# 1_Controller_A20_Power.net
KiCad netlist of a schematic drawn in Altium Designer
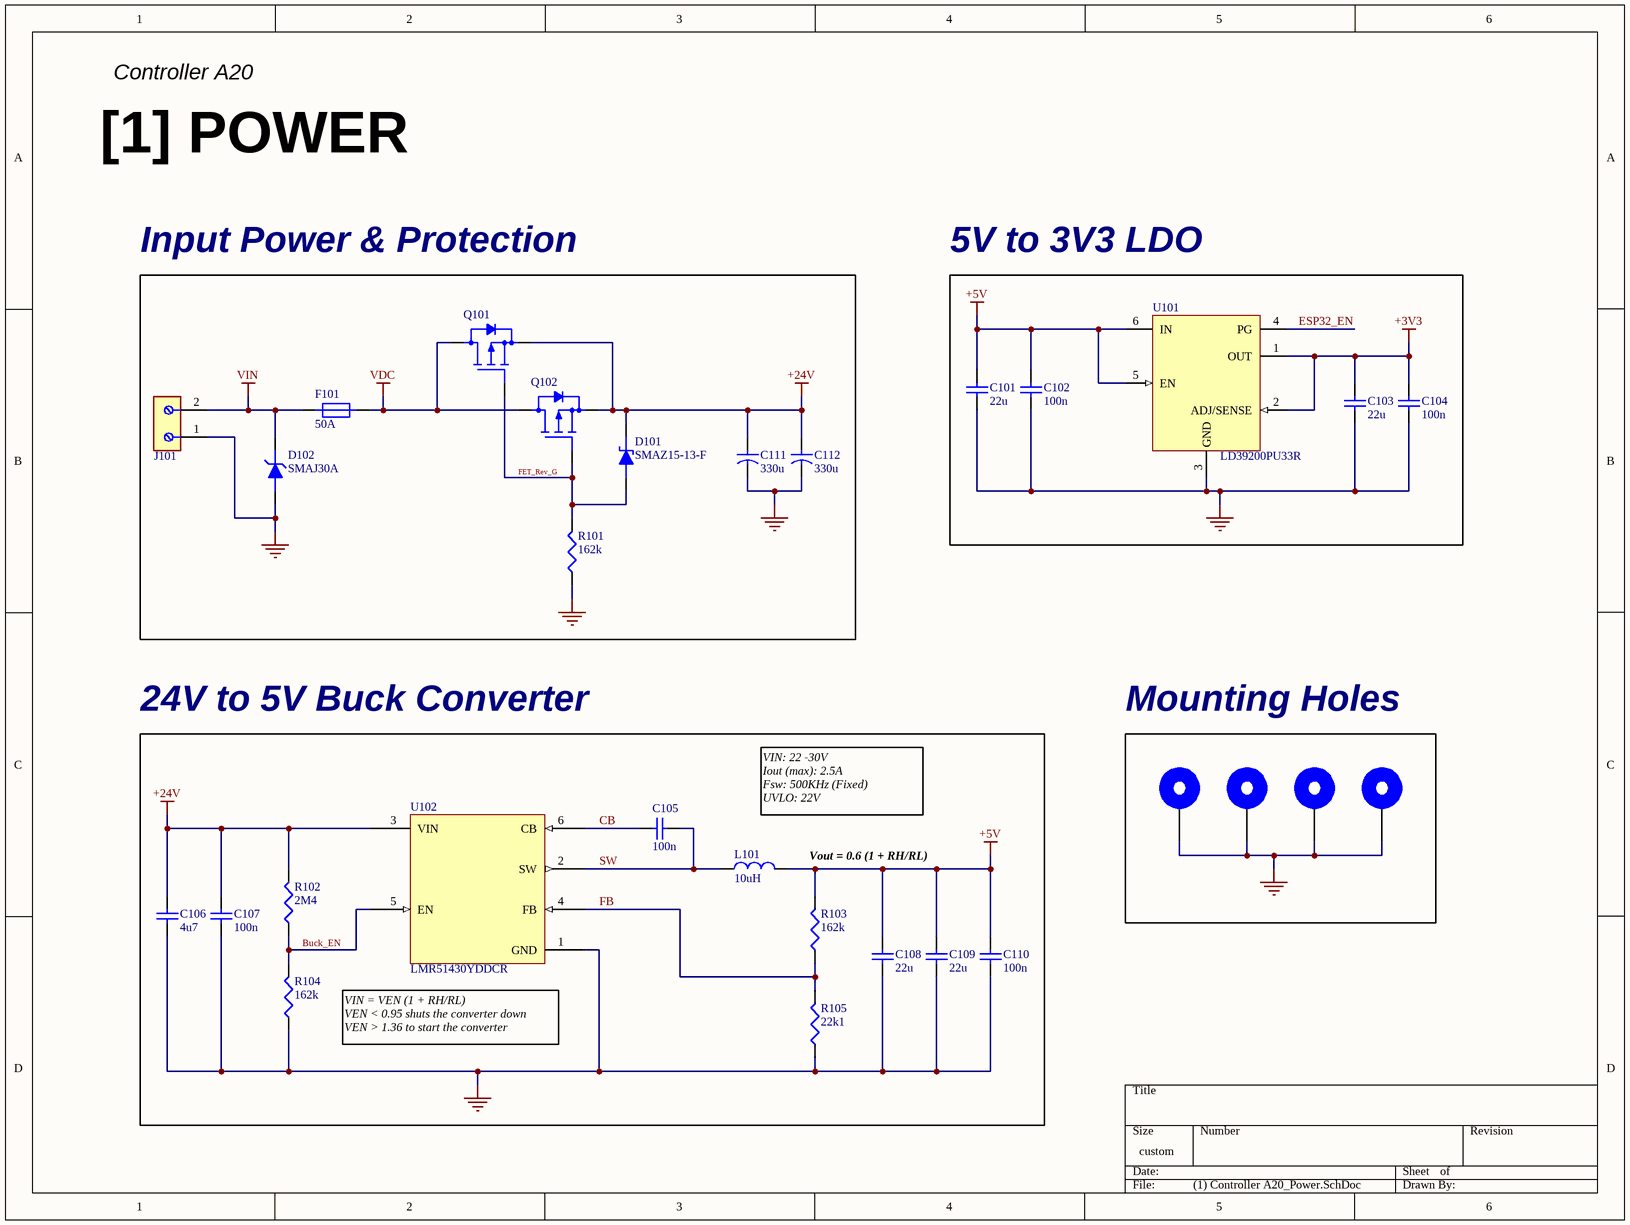
[diagram p0: (1) Controller A20_Power.SchDoc]

(export (version "E")
  (design (tool "Eeschema 10.0.6"))
  (components
    (comp (ref "C101")
      (value "22u")
      (footprint "C0805")
      (description "22 µF ±20% 25V Ceramic Capacitor X5R 0805 (2012 Metric)")
      (fields
        (field (name "MANUFACTURER") "Samsung Electro-Mechanics")
        (field (name "MFR. PART #") "CL21A226MAYNNNE")
      )
      (libsource (lib "Symbols") (part "CAP 22uF 25V"))
    )
    (comp (ref "C102")
      (value "100n")
      (footprint "C0603")
      (description "0.1 µF ±10% 50V Ceramic Capacitor X7R 0603 (1608 Metric)")
      (fields (field (name "MANUFACTURER") "KEMET") (field (name "MFR. PART #") "C0603C104K5RACTU"))
      (libsource (lib "Symbols") (part "CAP 100nF 50V"))
    )
    (comp (ref "C103")
      (value "22u")
      (footprint "C0805")
      (description "22 µF ±20% 25V Ceramic Capacitor X5R 0805 (2012 Metric)")
      (fields
        (field (name "MANUFACTURER") "Samsung Electro-Mechanics")
        (field (name "MFR. PART #") "CL21A226MAYNNNE")
      )
      (libsource (lib "Symbols") (part "CAP 22uF 25V"))
    )
    (comp (ref "C104")
      (value "100n")
      (footprint "C0603")
      (description "0.1 µF ±10% 50V Ceramic Capacitor X7R 0603 (1608 Metric)")
      (fields (field (name "MANUFACTURER") "KEMET") (field (name "MFR. PART #") "C0603C104K5RACTU"))
      (libsource (lib "Symbols") (part "CAP 100nF 50V"))
    )
    (comp (ref "C105")
      (value "100n")
      (footprint "C0603")
      (description "0.1 µF ±10% 50V Ceramic Capacitor X7R 0603 (1608 Metric)")
      (fields (field (name "MANUFACTURER") "KEMET") (field (name "MFR. PART #") "C0603C104K5RACTU"))
      (libsource (lib "Symbols") (part "CAP 100nF 50V"))
    )
    (comp (ref "C106")
      (value "4u7")
      (footprint "C0805")
      (description "4.7 µF ±20% 50V Ceramic Capacitor X7R 0805 (2012 Metric)")
      (fields
        (field (name "MANUFACTURER") "Murata Electronics")
        (field (name "MFR. PART #") "GRM21BZ71H475ME15K")
      )
      (libsource (lib "Symbols") (part "CAP 4.7uF 50V"))
    )
    (comp (ref "C107")
      (value "100n")
      (footprint "C0603")
      (description "0.1 µF ±10% 50V Ceramic Capacitor X7R 0603 (1608 Metric)")
      (fields (field (name "MANUFACTURER") "KEMET") (field (name "MFR. PART #") "C0603C104K5RACTU"))
      (libsource (lib "Symbols") (part "CAP 100nF 50V"))
    )
    (comp (ref "C108")
      (value "22u")
      (footprint "C0805")
      (description "22 µF ±20% 25V Ceramic Capacitor X5R 0805 (2012 Metric)")
      (fields
        (field (name "MANUFACTURER") "Samsung Electro-Mechanics")
        (field (name "MFR. PART #") "CL21A226MAYNNNE")
      )
      (libsource (lib "Symbols") (part "CAP 22uF 25V"))
    )
    (comp (ref "C109")
      (value "22u")
      (footprint "C0805")
      (description "22 µF ±20% 25V Ceramic Capacitor X5R 0805 (2012 Metric)")
      (fields
        (field (name "MANUFACTURER") "Samsung Electro-Mechanics")
        (field (name "MFR. PART #") "CL21A226MAYNNNE")
      )
      (libsource (lib "Symbols") (part "CAP 22uF 25V"))
    )
    (comp (ref "C110")
      (value "100n")
      (footprint "C0603")
      (description "0.1 µF ±10% 50V Ceramic Capacitor X7R 0603 (1608 Metric)")
      (fields (field (name "MANUFACTURER") "KEMET") (field (name "MFR. PART #") "C0603C104K5RACTU"))
      (libsource (lib "Symbols") (part "CAP 100nF 50V"))
    )
    (comp (ref "C111")
      (value "330u")
      (footprint "SMD CAP,D10.3xL10.3mm")
      (description "330 µF 50 V Aluminum Electrolytic Capacitors Radial, Can - SMD 2000 Hrs @ 105°C")
      (fields (field (name "MANUFACTURER") "Nichicon") (field (name "MFR. PART #") "UCM1H331MNL1GS"))
      (libsource (lib "Symbols") (part "Electrolytic CAP 330uF 50V"))
    )
    (comp (ref "C112")
      (value "330u")
      (footprint "SMD CAP,D10.3xL10.3mm")
      (description "330 µF 50 V Aluminum Electrolytic Capacitors Radial, Can - SMD 2000 Hrs @ 105°C")
      (fields (field (name "MANUFACTURER") "Nichicon") (field (name "MFR. PART #") "UCM1H331MNL1GS"))
      (libsource (lib "Symbols") (part "Electrolytic CAP 330uF 50V"))
    )
    (comp (ref "D101")
      (value "SMAZ15-13-F")
      (footprint "DO-214AC(SMA)")
      (description "Zener Diode 15 V 1 W ±5% Surface Mount SMA")
      (fields (field (name "MANUFACTURER") "Diodes Incorporated"))
      (libsource (lib "Symbols") (part "SMAZ15-13-F 15V Zener Diode"))
    )
    (comp (ref "D102")
      (value "SMAJ30A")
      (footprint "DO-214AC(SMA)")
      (description "48.4V Clamp 8.3A Ipp Tvs Diode Surface Mount DO-214AC")
      (fields (field (name "MANUFACTURER") "Würth Elektronik"))
      (libsource (lib "Symbols") (part "SMAJ30A TVS Diode 30VRWM"))
    )
    (comp (ref "F101")
      (value "50A")
      (footprint "SMD Fuse,12.2 x 4.5 x 4.5 mm")
      (description "50 A 250 V 80 V Fuse Board Mount (Cartridge Style Excluded) Surface Mount 2-SMD, Square End Block")
      (fields (field (name "MANUFACTURER") "Littelfuse Inc.") (field (name "MFR. PART #") "0456050.DRSDE"))
      (libsource (lib "Symbols") (part "0456050.DRSDE Fuse 50A"))
    )
    (comp (ref "J101")
      (value "691256610002")
      (footprint "10.16mm 2P STB")
      (description "2 Position Wire to Board Terminal Block Horizontal with Board 0.400\" (10.16mm) Through Hole")
      (fields (field (name "MANUFACTURER") "Würth Elektronik"))
      (libsource (lib "Symbols") (part "Terminal Block 2P 57A"))
    )
    (comp (ref "J102")
      (value "Mounting Hole D6mm H3mm")
      (footprint "MH D6mm H3mm")
      (libsource (lib "Symbols") (part "Mounting Hole D6mm H3mm"))
    )
    (comp (ref "J103")
      (value "Mounting Hole D6mm H3mm")
      (footprint "MH D6mm H3mm")
      (libsource (lib "Symbols") (part "Mounting Hole D6mm H3mm"))
    )
    (comp (ref "J104")
      (value "Mounting Hole D6mm H3mm")
      (footprint "MH D6mm H3mm")
      (libsource (lib "Symbols") (part "Mounting Hole D6mm H3mm"))
    )
    (comp (ref "J105")
      (value "Mounting Hole D6mm H3mm")
      (footprint "MH D6mm H3mm")
      (libsource (lib "Symbols") (part "Mounting Hole D6mm H3mm"))
    )
    (comp (ref "L101")
      (value "10uH")
      (footprint "L SMD 6.8x6.6")
      (description "10 µH Shielded Inductor 7 A 29.82mOhm Max Nonstandard")
      (fields (field (name "MANUFACTURER") "Pulse Electronics") (field (name "MFR. PART #") "PM5432.103NLT"))
      (libsource (lib "Symbols") (part "10uH 7A Inductor"))
    )
    (comp (ref "Q101")
      (value "XPH3R114MC,L1XHQ")
      (footprint "8-SOP Advance (5x5)")
      (description "P-Channel 40 V 100A (Ta) 960mW (Ta), 170W (Tc) Surface Mount 8-SOP Advance (5x5)")
      (fields (field (name "MANUFACTURER") "Toshiba Semiconductor and Storage"))
      (libsource (lib "Symbols") (part "MOSFET P-CH 40V 100A"))
    )
    (comp (ref "Q102")
      (value "XPH3R114MC,L1XHQ")
      (footprint "8-SOP Advance (5x5)")
      (description "P-Channel 40 V 100A (Ta) 960mW (Ta), 170W (Tc) Surface Mount 8-SOP Advance (5x5)")
      (fields (field (name "MANUFACTURER") "Toshiba Semiconductor and Storage"))
      (libsource (lib "Symbols") (part "MOSFET P-CH 40V 100A"))
    )
    (comp (ref "R101")
      (value "162k")
      (footprint "R0603")
      (description "162 kOhms ±1% 0.1W, 1/10W Chip Resistor 0603 (1608 Metric) Moisture Resistant Thick Film")
      (fields (field (name "MANUFACTURER") "YAGEO") (field (name "MFR. PART #") "RC0603FR-07162KL"))
      (libsource (lib "Symbols") (part "RES 162k"))
    )
    (comp (ref "R102")
      (value "2M4")
      (footprint "R0603")
      (description "2.4 MOhms ±1% 0.1W, 1/10W Chip Resistor 0603 (1608 Metric) Moisture Resistant Thick Film")
      (fields (field (name "MANUFACTURER") "YAGEO") (field (name "MFR. PART #") "RC0603FR-072M4L"))
      (libsource (lib "Symbols") (part "RES 2.4M"))
    )
    (comp (ref "R103")
      (value "162k")
      (footprint "R0603")
      (description "162 kOhms ±1% 0.1W, 1/10W Chip Resistor 0603 (1608 Metric) Moisture Resistant Thick Film")
      (fields (field (name "MANUFACTURER") "YAGEO") (field (name "MFR. PART #") "RC0603FR-07162KL"))
      (libsource (lib "Symbols") (part "RES 162k"))
    )
    (comp (ref "R104")
      (value "162k")
      (footprint "R0603")
      (description "162 kOhms ±1% 0.1W, 1/10W Chip Resistor 0603 (1608 Metric) Moisture Resistant Thick Film")
      (fields (field (name "MANUFACTURER") "YAGEO") (field (name "MFR. PART #") "RC0603FR-07162KL"))
      (libsource (lib "Symbols") (part "RES 162k"))
    )
    (comp (ref "R105")
      (value "22k1")
      (footprint "R0603")
      (description "22.1 kOhms ±1% 0.1W, 1/10W Chip Resistor 0603 (1608 Metric) Thin Film")
      (fields (field (name "MANUFACTURER") "YAGEO") (field (name "MFR. PART #") "RT0603FRE0722K1L"))
      (libsource (lib "Symbols") (part "RES 22.1k"))
    )
    (comp (ref "U101")
      (value "LD39200PU33R")
      (footprint "DFN-6(3x3)")
      (description "Linear Voltage Regulator IC Positive Fixed 1 Output 2A 6-DFN (3x3)")
      (fields (field (name "MANUFACTURER") "STMicroelectronics"))
      (libsource (lib "Symbols") (part "LDO 3V3 2A"))
    )
    (comp (ref "U102")
      (value "LMR51430YDDCR")
      (footprint "SOT-23-6")
      (description "Buck Switching Regulator IC Positive Adjustable 0.6V 1 Output 3A SOT-23-6 Thin, TSOT-23-6")
      (fields (field (name "MANUFACTURER") "Texas Instruments"))
      (libsource (lib "Symbols") (part "LMR51430YDDCR Buck Converter"))
    )
  )
  (nets
    (net (code "1") (name "+3V3") (class "Default")
      (node (ref "C103") (pin "2") (pinfunction "2_2") (pintype "passive"))
      (node (ref "C104") (pin "2") (pinfunction "2_2") (pintype "passive"))
      (node (ref "U101") (pin "1") (pinfunction "OUT_1") (pintype "power_in"))
      (node (ref "U101") (pin "2") (pinfunction "ADJ/SENSE_2") (pintype "input"))
    )
    (net (code "2") (name "+5V") (class "Default")
      (node (ref "C101") (pin "2") (pinfunction "2_2") (pintype "passive"))
      (node (ref "C102") (pin "2") (pinfunction "2_2") (pintype "passive"))
      (node (ref "C108") (pin "2") (pinfunction "2_2") (pintype "passive"))
      (node (ref "C109") (pin "2") (pinfunction "2_2") (pintype "passive"))
      (node (ref "C110") (pin "2") (pinfunction "2_2") (pintype "passive"))
      (node (ref "L101") (pin "2") (pinfunction "2_2") (pintype "passive"))
      (node (ref "R103") (pin "2") (pinfunction "2_2") (pintype "passive"))
      (node (ref "U101") (pin "5") (pinfunction "EN_5") (pintype "input"))
      (node (ref "U101") (pin "6") (pinfunction "IN_6") (pintype "power_in"))
    )
    (net (code "3") (name "+24V") (class "Default")
      (node (ref "C106") (pin "2") (pinfunction "2_2") (pintype "passive"))
      (node (ref "C107") (pin "2") (pinfunction "2_2") (pintype "passive"))
      (node (ref "C111") (pin "1") (pinfunction "1_1") (pintype "passive"))
      (node (ref "C112") (pin "1") (pinfunction "1_1") (pintype "passive"))
      (node (ref "D101") (pin "2") (pinfunction "2_2") (pintype "passive"))
      (node (ref "Q101") (pin "1") (pinfunction "1_1") (pintype "passive"))
      (node (ref "Q102") (pin "1") (pinfunction "1_1") (pintype "passive"))
      (node (ref "R102") (pin "2") (pinfunction "2_2") (pintype "passive"))
      (node (ref "U102") (pin "3") (pinfunction "VIN_3") (pintype "power_in"))
    )
    (net (code "4") (name "/Buck_EN") (class "Default")
      (node (ref "R102") (pin "1") (pinfunction "1_1") (pintype "passive"))
      (node (ref "R104") (pin "2") (pinfunction "2_2") (pintype "passive"))
      (node (ref "U102") (pin "5") (pinfunction "EN_5") (pintype "input"))
    )
    (net (code "5") (name "/CB") (class "Default")
      (node (ref "C105") (pin "1") (pinfunction "1_1") (pintype "passive"))
      (node (ref "U102") (pin "6") (pinfunction "CB_6") (pintype "input"))
    )
    (net (code "6") (name "/ESP32_EN") (class "Default")
      (node (ref "U101") (pin "4") (pinfunction "PG_4") (pintype "tri_state"))
    )
    (net (code "7") (name "/FB") (class "Default")
      (node (ref "R103") (pin "1") (pinfunction "1_1") (pintype "passive"))
      (node (ref "R105") (pin "2") (pinfunction "2_2") (pintype "passive"))
      (node (ref "U102") (pin "4") (pinfunction "FB_4") (pintype "input"))
    )
    (net (code "8") (name "/FET_Rev_G") (class "Default")
      (node (ref "D101") (pin "1") (pinfunction "1_1") (pintype "passive"))
      (node (ref "Q101") (pin "4") (pinfunction "4_4") (pintype "passive"))
      (node (ref "Q102") (pin "4") (pinfunction "4_4") (pintype "passive"))
      (node (ref "R101") (pin "2") (pinfunction "2_2") (pintype "passive"))
    )
    (net (code "9") (name "/SW") (class "Default")
      (node (ref "C105") (pin "2") (pinfunction "2_2") (pintype "passive"))
      (node (ref "L101") (pin "1") (pinfunction "1_1") (pintype "passive"))
      (node (ref "U102") (pin "2") (pinfunction "SW_2") (pintype "output"))
    )
    (net (code "10") (name "GND") (class "Default")
      (node (ref "C101") (pin "1") (pinfunction "1_1") (pintype "passive"))
      (node (ref "C102") (pin "1") (pinfunction "1_1") (pintype "passive"))
      (node (ref "C103") (pin "1") (pinfunction "1_1") (pintype "passive"))
      (node (ref "C104") (pin "1") (pinfunction "1_1") (pintype "passive"))
      (node (ref "C106") (pin "1") (pinfunction "1_1") (pintype "passive"))
      (node (ref "C107") (pin "1") (pinfunction "1_1") (pintype "passive"))
      (node (ref "C108") (pin "1") (pinfunction "1_1") (pintype "passive"))
      (node (ref "C109") (pin "1") (pinfunction "1_1") (pintype "passive"))
      (node (ref "C110") (pin "1") (pinfunction "1_1") (pintype "passive"))
      (node (ref "C111") (pin "2") (pinfunction "2_2") (pintype "passive"))
      (node (ref "C112") (pin "2") (pinfunction "2_2") (pintype "passive"))
      (node (ref "D102") (pin "1") (pinfunction "1_1") (pintype "passive"))
      (node (ref "J101") (pin "1") (pinfunction "1_1") (pintype "passive"))
      (node (ref "J102") (pin "1") (pinfunction "1_1") (pintype "passive"))
      (node (ref "J103") (pin "1") (pinfunction "1_1") (pintype "passive"))
      (node (ref "J104") (pin "1") (pinfunction "1_1") (pintype "passive"))
      (node (ref "J105") (pin "1") (pinfunction "1_1") (pintype "passive"))
      (node (ref "R101") (pin "1") (pinfunction "1_1") (pintype "passive"))
      (node (ref "R104") (pin "1") (pinfunction "1_1") (pintype "passive"))
      (node (ref "R105") (pin "1") (pinfunction "1_1") (pintype "passive"))
      (node (ref "U101") (pin "3") (pinfunction "GND_3") (pintype "power_in"))
      (node (ref "U102") (pin "1") (pinfunction "GND_1") (pintype "power_in"))
    )
    (net (code "11") (name "VDC") (class "Default")
      (node (ref "F101") (pin "1") (pinfunction "1_1") (pintype "passive"))
      (node (ref "Q101") (pin "5") (pinfunction "5_5") (pintype "passive"))
      (node (ref "Q102") (pin "5") (pinfunction "5_5") (pintype "passive"))
    )
    (net (code "12") (name "VIN") (class "Default")
      (node (ref "D102") (pin "2") (pinfunction "2_2") (pintype "passive"))
      (node (ref "F101") (pin "2") (pinfunction "2_2") (pintype "passive"))
      (node (ref "J101") (pin "2") (pinfunction "2_2") (pintype "passive"))
    )
  )
)
